# MR_UartConnector.net
KiCad netlist of a schematic drawn in Altium Designer
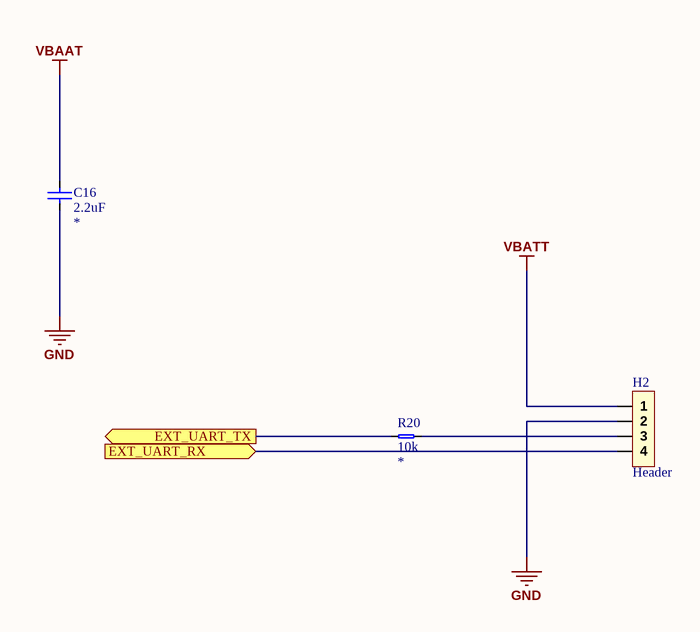
[diagram p0: MR_UartConnector.SchDoc]

(export (version "E")
  (design (tool "Eeschema 10.0.6"))
  (components
    (comp (ref "C16")
      (value "2.2uF")
      (footprint "0603_CAP_LD")
      (description "Ceramic Capacitor")
      (fields (field (name "PACKAGE") "*") (field (name "Comment") "CerCap"))
      (libsource (lib "MiniRobot") (part "CerCap"))
    )
    (comp (ref "H2")
      (value "Header")
      (footprint "HE14 1x4 Straight")
      (description "Header 4x1 PIns")
      (libsource (lib "MiniRobot") (part "Header_4x1"))
    )
    (comp (ref "R20")
      (value "10k")
      (footprint "0603_RES_LD")
      (description "Resistor")
      (fields (field (name "PACKAGE") "*"))
      (libsource (lib "MiniRobot") (part "Resistor"))
    )
  )
  (nets
    (net (code "1") (name "/EXT_UART_RX") (class "Default")
      (node (ref "H2") (pin "1") (pinfunction "4_1") (pintype "passive"))
    )
    (net (code "2") (name "/EXT_UART_TX") (class "Default")
      (node (ref "R20") (pin "1") (pinfunction "1_1") (pintype "passive"))
    )
    (net (code "3") (name "GND") (class "Default")
      (node (ref "C16") (pin "2") (pinfunction "2_2") (pintype "passive"))
      (node (ref "H2") (pin "3") (pinfunction "2_3") (pintype "passive"))
    )
    (net (code "4") (name "Net-(H2-3)") (class "Default")
      (node (ref "H2") (pin "2") (pinfunction "3_2") (pintype "passive"))
      (node (ref "R20") (pin "2") (pinfunction "2_2") (pintype "passive"))
    )
    (net (code "5") (name "VBAAT") (class "Default")
      (node (ref "C16") (pin "1") (pinfunction "1_1") (pintype "passive"))
    )
    (net (code "6") (name "VBATT") (class "Default")
      (node (ref "H2") (pin "4") (pinfunction "1_4") (pintype "passive"))
    )
  )
)
